# OSD.net
KiCad netlist of a schematic drawn in Altium Designer
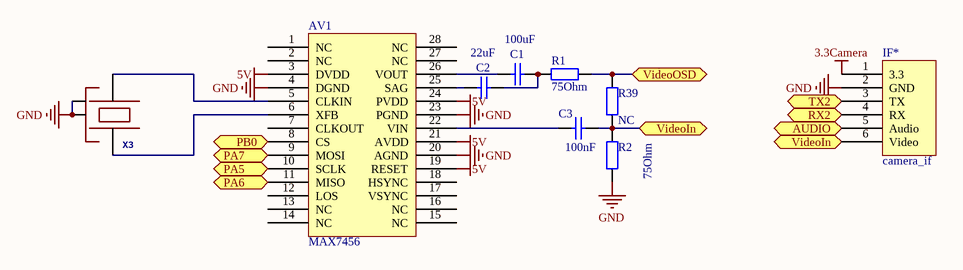
[diagram p0: OSD.SchDoc]

(export (version "E")
  (design (tool "Eeschema 10.0.6"))
  (components
    (comp (ref "AV1")
      (value "MAX7456")
      (footprint "28TSSOP")
      (libsource (lib "complements") (part "MAX7456"))
    )
    (comp (ref "C1")
      (value "100uF")
      (footprint "1210")
      (description "Capacitor (Semiconductor SIM Model)")
      (fields (field (name "PUBLISHER") "Altium Limited"))
      (libsource (lib "Miscellaneous Devices") (part "Cap Semi"))
    )
    (comp (ref "C2")
      (value "22uF")
      (footprint "1210")
      (description "Capacitor (Semiconductor SIM Model)")
      (fields (field (name "PUBLISHER") "Altium Limited"))
      (libsource (lib "Miscellaneous Devices") (part "Cap Semi"))
    )
    (comp (ref "C3")
      (value "100nF")
      (footprint "0603")
      (description "Capacitor (Semiconductor SIM Model)")
      (fields (field (name "PUBLISHER") "Altium Limited"))
      (libsource (lib "Miscellaneous Devices") (part "Cap Semi"))
    )
    (comp (ref "IF*")
      (value "camera_if")
      (footprint "WFRSM125")
      (libsource (lib "RTC6705") (part "camera_if"))
    )
    (comp (ref "R1")
      (value "75Ohm")
      (footprint "0603")
      (description "Resistor")
      (fields (field (name "PUBLISHER") "Altium Limited"))
      (libsource (lib "") (part "Res2_1"))
    )
    (comp (ref "R2")
      (value "75Ohm")
      (footprint "0603")
      (description "Resistor")
      (fields (field (name "PUBLISHER") "Altium Limited"))
      (libsource (lib "Miscellaneous Devices") (part "Res2"))
    )
    (comp (ref "R39")
      (value "NC")
      (footprint "0603")
      (description "Resistor")
      (fields (field (name "PUBLISHER") "Altium Limited"))
      (libsource (lib "Miscellaneous Devices") (part "Res2"))
    )
    (comp (ref "X3")
      (value "8mhz")
      (footprint "OSCILLATOR-3.2X2.5")
      (description "Crystal Oscillator in 3.2x2.5 SMD")
      (libsource (lib "pixhawk2") (part "OSCILLATOR-3.2X2.5"))
    )
  )
  (nets
    (net (code "1") (name "/AUDIO") (class "Default")
      (node (ref "IF*") (pin "5") (pinfunction "Audio_5") (pintype "passive"))
    )
    (net (code "2") (name "/PA5") (class "Default")
      (node (ref "AV1") (pin "10") (pinfunction "SCLK_10") (pintype "passive"))
    )
    (net (code "3") (name "/PA6") (class "Default")
      (node (ref "AV1") (pin "11") (pinfunction "MISO_11") (pintype "passive"))
    )
    (net (code "4") (name "/PA7") (class "Default")
      (node (ref "AV1") (pin "9") (pinfunction "MOSI_9") (pintype "passive"))
    )
    (net (code "5") (name "/PB0") (class "Default")
      (node (ref "AV1") (pin "8") (pinfunction "CS_8") (pintype "passive"))
    )
    (net (code "6") (name "/RX2") (class "Default")
      (node (ref "IF*") (pin "4") (pinfunction "RX_4") (pintype "passive"))
    )
    (net (code "7") (name "/TX2") (class "Default")
      (node (ref "IF*") (pin "3") (pinfunction "TX_3") (pintype "passive"))
    )
    (net (code "8") (name "/VideoIn") (class "Default")
      (node (ref "C3") (pin "2") (pinfunction "2_2") (pintype "passive"))
      (node (ref "IF*") (pin "6") (pinfunction "Video_6") (pintype "passive"))
      (node (ref "R2") (pin "2") (pinfunction "2_2") (pintype "passive"))
      (node (ref "R39") (pin "1") (pinfunction "1_1") (pintype "passive"))
    )
    (net (code "9") (name "/VideoOSD") (class "Default")
      (node (ref "R1") (pin "2") (pinfunction "2_2") (pintype "passive"))
      (node (ref "R39") (pin "2") (pinfunction "2_2") (pintype "passive"))
    )
    (net (code "10") (name "3.3Camera") (class "Default")
      (node (ref "IF*") (pin "1") (pinfunction "3.3_1") (pintype "passive"))
    )
    (net (code "11") (name "5V") (class "Default")
      (node (ref "AV1") (pin "19") (pinfunction "RESET_19") (pintype "passive"))
      (node (ref "AV1") (pin "21") (pinfunction "AVDD_21") (pintype "passive"))
      (node (ref "AV1") (pin "24") (pinfunction "PVDD_24") (pintype "passive"))
      (node (ref "AV1") (pin "3") (pinfunction "DVDD_3") (pintype "passive"))
    )
    (net (code "12") (name "GND") (class "Default")
      (node (ref "AV1") (pin "20") (pinfunction "AGND_20") (pintype "passive"))
      (node (ref "AV1") (pin "23") (pinfunction "PGND_23") (pintype "passive"))
      (node (ref "AV1") (pin "4") (pinfunction "DGND_4") (pintype "passive"))
      (node (ref "IF*") (pin "2") (pinfunction "GND_2") (pintype "passive"))
      (node (ref "R2") (pin "1") (pinfunction "1_1") (pintype "passive"))
      (node (ref "X3") (pin "2") (pinfunction "NC_2_2") (pintype "open_emitter"))
      (node (ref "X3") (pin "4") (pinfunction "NC_4_4") (pintype "open_emitter"))
    )
    (net (code "13") (name "Net-(AV1-CLKIN)") (class "Default")
      (node (ref "AV1") (pin "5") (pinfunction "CLKIN_5") (pintype "passive"))
      (node (ref "X3") (pin "1") (pinfunction "1_1") (pintype "passive"))
    )
    (net (code "14") (name "Net-(AV1-SAG)") (class "Default")
      (node (ref "AV1") (pin "25") (pinfunction "SAG_25") (pintype "passive"))
      (node (ref "C2") (pin "1") (pinfunction "1_1") (pintype "passive"))
    )
    (net (code "15") (name "Net-(AV1-VIN)") (class "Default")
      (node (ref "AV1") (pin "22") (pinfunction "VIN_22") (pintype "passive"))
      (node (ref "C3") (pin "1") (pinfunction "1_1") (pintype "passive"))
    )
    (net (code "16") (name "Net-(AV1-VOUT)") (class "Default")
      (node (ref "AV1") (pin "26") (pinfunction "VOUT_26") (pintype "passive"))
      (node (ref "C1") (pin "1") (pinfunction "1_1") (pintype "passive"))
    )
    (net (code "17") (name "Net-(AV1-XFB)") (class "Default")
      (node (ref "AV1") (pin "6") (pinfunction "XFB_6") (pintype "passive"))
      (node (ref "X3") (pin "3") (pinfunction "3_3") (pintype "passive"))
    )
    (net (code "18") (name "Net-(C1-Pad2)") (class "Default")
      (node (ref "C1") (pin "2") (pinfunction "2_2") (pintype "passive"))
      (node (ref "C2") (pin "2") (pinfunction "2_2") (pintype "passive"))
      (node (ref "R1") (pin "1") (pinfunction "1_1") (pintype "passive"))
    )
    (net (code "19") (name "unconnected-(AV1-CLKOUT-Pad7)") (class "Default")
      (node (ref "AV1") (pin "7") (pinfunction "CLKOUT_7") (pintype "passive"))
    )
    (net (code "20") (name "unconnected-(AV1-HSYNC-Pad18)") (class "Default")
      (node (ref "AV1") (pin "18") (pinfunction "HSYNC_18") (pintype "passive"))
    )
    (net (code "21") (name "unconnected-(AV1-LOS-Pad12)") (class "Default")
      (node (ref "AV1") (pin "12") (pinfunction "LOS_12") (pintype "passive"))
    )
    (net (code "22") (name "unconnected-(AV1-NC-Pad1)") (class "Default")
      (node (ref "AV1") (pin "1") (pinfunction "NC_1") (pintype "passive"))
    )
    (net (code "23") (name "unconnected-(AV1-NC-Pad2)") (class "Default")
      (node (ref "AV1") (pin "2") (pinfunction "NC_2") (pintype "passive"))
    )
    (net (code "24") (name "unconnected-(AV1-NC-Pad13)") (class "Default")
      (node (ref "AV1") (pin "13") (pinfunction "NC_13") (pintype "passive"))
    )
    (net (code "25") (name "unconnected-(AV1-NC-Pad14)") (class "Default")
      (node (ref "AV1") (pin "14") (pinfunction "NC_14") (pintype "passive"))
    )
    (net (code "26") (name "unconnected-(AV1-NC-Pad15)") (class "Default")
      (node (ref "AV1") (pin "15") (pinfunction "NC_15") (pintype "passive"))
    )
    (net (code "27") (name "unconnected-(AV1-NC-Pad16)") (class "Default")
      (node (ref "AV1") (pin "16") (pinfunction "NC_16") (pintype "passive"))
    )
    (net (code "28") (name "unconnected-(AV1-NC-Pad27)") (class "Default")
      (node (ref "AV1") (pin "27") (pinfunction "NC_27") (pintype "passive"))
    )
    (net (code "29") (name "unconnected-(AV1-NC-Pad28)") (class "Default")
      (node (ref "AV1") (pin "28") (pinfunction "NC_28") (pintype "passive"))
    )
    (net (code "30") (name "unconnected-(AV1-VSYNC-Pad17)") (class "Default")
      (node (ref "AV1") (pin "17") (pinfunction "VSYNC_17") (pintype "passive"))
    )
  )
)
